# Lighting.net
KiCad netlist of a schematic drawn in Altium Designer
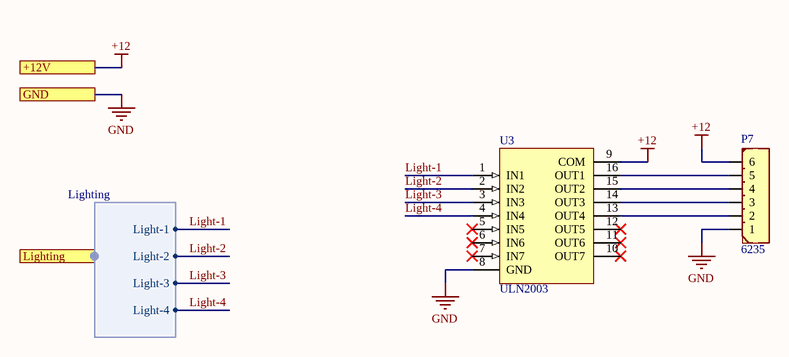
[diagram p0: Lighting.SchDoc]

(export (version "E")
  (design (tool "Eeschema 10.0.6"))
  (components
    (comp (ref "P7")
      (value "6'Pin")
      (footprint "645006114822")
      (description "6'Pin Power Connector")
      (fields (field (name "INFLOW") "6235") (field (name "VALIDATION") "Valid"))
      (libsource (lib "aKaReZa") (part "Con_Power_6_PC_V"))
    )
    (comp (ref "U3")
      (value "ULN2003")
      (footprint "SO16_M")
      (description "Seven darlington array drivers")
      (fields (field (name "VALIDATION") "Valid"))
      (libsource (lib "aKaReZa") (part "IC_Driver_ULN2003"))
    )
  )
  (nets
    (net (code "2") (name "+12") (class "Default")
      (node (ref "P7") (pin "6") (pinfunction "6_6") (pintype "passive"))
      (node (ref "U3") (pin "9") (pinfunction "COM_9") (pintype "passive"))
    )
    (net (code "3") (name "/Light-1") (class "Default")
      (node (ref "U3") (pin "1") (pinfunction "IN1_1") (pintype "input"))
    )
    (net (code "4") (name "/Light-2") (class "Default")
      (node (ref "U3") (pin "2") (pinfunction "IN2_2") (pintype "input"))
    )
    (net (code "5") (name "/Light-3") (class "Default")
      (node (ref "U3") (pin "3") (pinfunction "IN3_3") (pintype "input"))
    )
    (net (code "6") (name "/Light-4") (class "Default")
      (node (ref "U3") (pin "4") (pinfunction "IN4_4") (pintype "input"))
    )
    (net (code "8") (name "GND") (class "Default")
      (node (ref "P7") (pin "1") (pinfunction "1_1") (pintype "passive"))
      (node (ref "U3") (pin "8") (pinfunction "GND_8") (pintype "power_in"))
    )
    (net (code "9") (name "Net-(U3-OUT1)") (class "Default")
      (node (ref "P7") (pin "5") (pinfunction "5_5") (pintype "passive"))
      (node (ref "U3") (pin "16") (pinfunction "OUT1_16") (pintype "open_collector"))
    )
    (net (code "10") (name "Net-(U3-OUT2)") (class "Default")
      (node (ref "P7") (pin "4") (pinfunction "4_4") (pintype "passive"))
      (node (ref "U3") (pin "15") (pinfunction "OUT2_15") (pintype "open_collector"))
    )
    (net (code "11") (name "Net-(U3-OUT3)") (class "Default")
      (node (ref "P7") (pin "3") (pinfunction "3_3") (pintype "passive"))
      (node (ref "U3") (pin "14") (pinfunction "OUT3_14") (pintype "open_collector"))
    )
    (net (code "12") (name "Net-(U3-OUT4)") (class "Default")
      (node (ref "P7") (pin "2") (pinfunction "2_2") (pintype "passive"))
      (node (ref "U3") (pin "13") (pinfunction "OUT4_13") (pintype "open_collector"))
    )
    (net (code "13") (name "unconnected-(U3-IN5-Pad5)") (class "Default")
      (node (ref "U3") (pin "5") (pinfunction "IN5_5") (pintype "input+no_connect"))
    )
    (net (code "14") (name "unconnected-(U3-IN6-Pad6)") (class "Default")
      (node (ref "U3") (pin "6") (pinfunction "IN6_6") (pintype "input+no_connect"))
    )
    (net (code "15") (name "unconnected-(U3-IN7-Pad7)") (class "Default")
      (node (ref "U3") (pin "7") (pinfunction "IN7_7") (pintype "input+no_connect"))
    )
    (net (code "16") (name "unconnected-(U3-OUT5-Pad12)") (class "Default")
      (node (ref "U3") (pin "12") (pinfunction "OUT5_12") (pintype "open_collector+no_connect"))
    )
    (net (code "17") (name "unconnected-(U3-OUT6-Pad11)") (class "Default")
      (node (ref "U3") (pin "11") (pinfunction "OUT6_11") (pintype "open_collector+no_connect"))
    )
    (net (code "18") (name "unconnected-(U3-OUT7-Pad10)") (class "Default")
      (node (ref "U3") (pin "10") (pinfunction "OUT7_10") (pintype "open_collector+no_connect"))
    )
  )
)
